# Controller_Board_Interface.net
KiCad netlist of a schematic drawn in Altium Designer
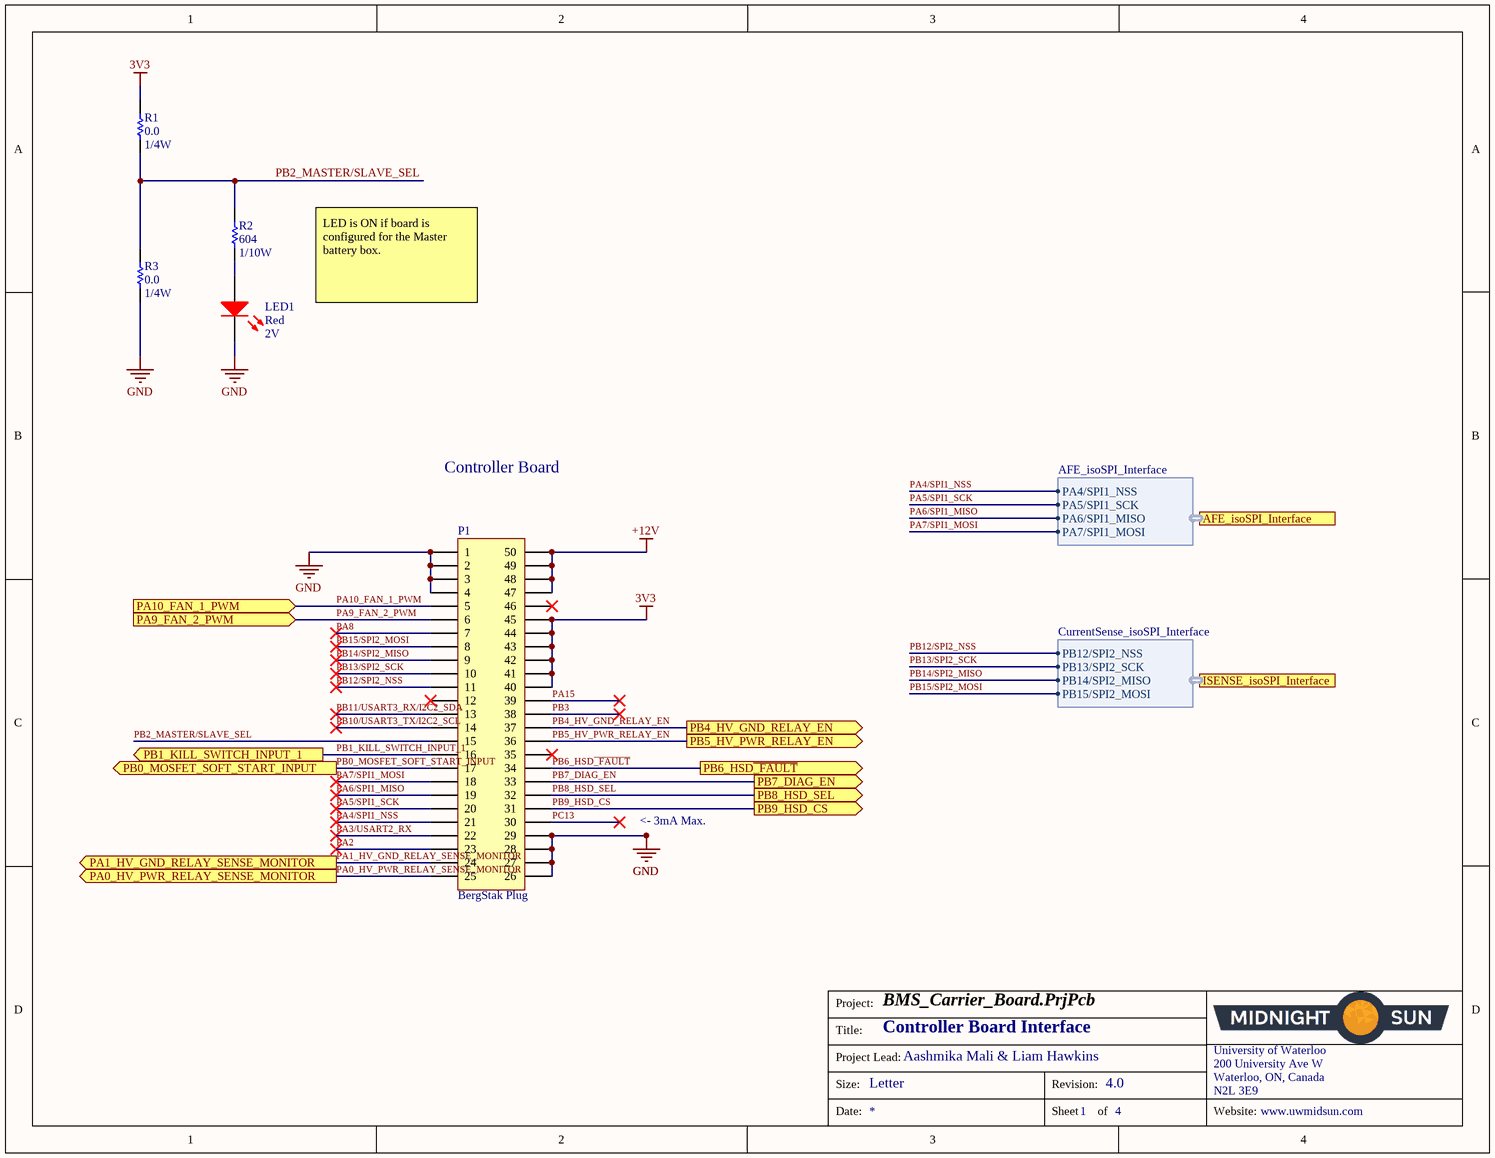
[diagram p0: Controller_Board_Interface.SchDoc]

(export (version "E")
  (design (tool "Eeschema 10.0.6"))
  (components
    (comp (ref "LED1")
      (value "LED RED CLEAR 2V 0603")
      (footprint "LED_0603")
      (description "Red 631nm LED Indication - Discrete 2V 0603 (1608 Metric)")
      (fields
        (field (name "MANUFACTURER") "Wurth Electronics Inc.")
        (field (name "MANUFACTURER PART NUMBER") "150060RS75000")
        (field (name "COLOR") "Red")
        (field (name "VOLTAGE - FORWARD (VF) (TYP)") "2V")
      )
      (libsource (lib "Schematic Diagrams") (part "LED RED CLEAR 2V 0603"))
    )
    (comp (ref "P1")
      (value "CONN 50POS Bergstak Plug 0.02\"")
      (footprint "CONN, Bergstak 50 Pos Plug")
      (description "50 Position Connector Plug, Outer Shroud Contacts Surface Mount Gold")
      (fields (field (name "SERIES") "BergStak Plug"))
      (libsource (lib "Schematic Diagrams") (part "CONN 50POS Bergstak Plug 0.02{dblquote}"))
    )
    (comp (ref "R1")
      (value "RES 0.0 OHM 1/4W 0603")
      (footprint "RES, 0603")
      (description "RES SMD 0.0 OHM JUMPER 1/4W 0603")
      (fields (field (name "RESISTANCE") "0.0") (field (name "POWER (WATTS)") "1/4W"))
      (libsource (lib "Schematic Diagrams") (part "RES 0.0 OHM 1/4W 0603"))
    )
    (comp (ref "R2")
      (value "RES 604 OHM 1% 1/10W 0603")
      (footprint "RES, 0603")
      (description "RES SMD 604 OHM 1% 1/10W 0603")
      (fields
        (field (name "TOLERANCE") "±1%")
        (field (name "RESISTANCE") "604")
        (field (name "POWER") "1/10W")
      )
      (libsource (lib "Schematic Diagrams") (part "RES 604 OHM 1% 1/10W 0603"))
    )
    (comp (ref "R3")
      (value "RES 0.0 OHM 1/4W 0603")
      (footprint "RES, 0603")
      (description "RES SMD 0.0 OHM JUMPER 1/4W 0603")
      (fields (field (name "RESISTANCE") "0.0") (field (name "POWER (WATTS)") "1/4W"))
      (libsource (lib "Schematic Diagrams") (part "RES 0.0 OHM 1/4W 0603"))
    )
  )
  (nets
    (net (code "3") (name "+12V") (class "Default")
      (node (ref "P1") (pin "47") (pinfunction "47_47") (pintype "passive"))
      (node (ref "P1") (pin "48") (pinfunction "48_48") (pintype "passive"))
      (node (ref "P1") (pin "49") (pinfunction "49_49") (pintype "passive"))
      (node (ref "P1") (pin "50") (pinfunction "50_50") (pintype "passive"))
    )
    (net (code "4") (name "/PA0_HV_PWR_RELAY_SENSE_MONITOR") (class "Default")
      (node (ref "P1") (pin "25") (pinfunction "25_25") (pintype "passive"))
    )
    (net (code "5") (name "/PA1_HV_GND_RELAY_SENSE_MONITOR") (class "Default")
      (node (ref "P1") (pin "24") (pinfunction "24_24") (pintype "passive"))
    )
    (net (code "6") (name "/PA2") (class "Default")
      (node (ref "P1") (pin "23") (pinfunction "23_23") (pintype "passive+no_connect"))
    )
    (net (code "7") (name "/PA3{slash}USART2_RX") (class "Default")
      (node (ref "P1") (pin "22") (pinfunction "22_22") (pintype "passive+no_connect"))
    )
    (net (code "8") (name "/PA4{slash}SPI1_NSS") (class "Default")
      (node (ref "P1") (pin "21") (pinfunction "21_21") (pintype "passive"))
    )
    (net (code "9") (name "/PA5{slash}SPI1_SCK") (class "Default")
      (node (ref "P1") (pin "20") (pinfunction "20_20") (pintype "passive"))
    )
    (net (code "10") (name "/PA6{slash}SPI1_MISO") (class "Default")
      (node (ref "P1") (pin "19") (pinfunction "19_19") (pintype "passive"))
    )
    (net (code "11") (name "/PA7{slash}SPI1_MOSI") (class "Default")
      (node (ref "P1") (pin "18") (pinfunction "18_18") (pintype "passive"))
    )
    (net (code "12") (name "/PA8") (class "Default")
      (node (ref "P1") (pin "7") (pinfunction "7_7") (pintype "passive+no_connect"))
    )
    (net (code "13") (name "/PA9_FAN_2_PWM") (class "Default")
      (node (ref "P1") (pin "6") (pinfunction "6_6") (pintype "passive"))
    )
    (net (code "14") (name "/PA10_FAN_1_PWM") (class "Default")
      (node (ref "P1") (pin "5") (pinfunction "5_5") (pintype "passive"))
    )
    (net (code "15") (name "/PA15") (class "Default")
      (node (ref "P1") (pin "39") (pinfunction "39_39") (pintype "passive+no_connect"))
    )
    (net (code "16") (name "/PB0_MOSFET_SOFT_START_INPUT") (class "Default")
      (node (ref "P1") (pin "17") (pinfunction "17_17") (pintype "passive"))
    )
    (net (code "17") (name "/PB1_KILL_SWITCH_INPUT_1") (class "Default")
      (node (ref "P1") (pin "16") (pinfunction "16_16") (pintype "passive"))
    )
    (net (code "18") (name "/PB2_MASTER{slash}SLAVE_SEL") (class "Default")
      (node (ref "P1") (pin "15") (pinfunction "15_15") (pintype "passive"))
      (node (ref "R1") (pin "2") (pinfunction "2_2") (pintype "passive"))
      (node (ref "R2") (pin "1") (pinfunction "1_1") (pintype "passive"))
      (node (ref "R3") (pin "1") (pinfunction "1_1") (pintype "passive"))
    )
    (net (code "19") (name "/PB3") (class "Default")
      (node (ref "P1") (pin "38") (pinfunction "38_38") (pintype "passive+no_connect"))
    )
    (net (code "20") (name "/PB4_HV_GND_RELAY_EN") (class "Default")
      (node (ref "P1") (pin "37") (pinfunction "37_37") (pintype "passive"))
    )
    (net (code "21") (name "/PB5_HV_PWR_RELAY_EN") (class "Default")
      (node (ref "P1") (pin "36") (pinfunction "36_36") (pintype "passive"))
    )
    (net (code "22") (name "/PB6_HSD~{_FAULT}") (class "Default")
      (node (ref "P1") (pin "34") (pinfunction "34_34") (pintype "passive"))
    )
    (net (code "23") (name "/PB7_DIAG_EN") (class "Default")
      (node (ref "P1") (pin "33") (pinfunction "33_33") (pintype "passive"))
    )
    (net (code "24") (name "/PB8_HSD_SEL") (class "Default")
      (node (ref "P1") (pin "32") (pinfunction "32_32") (pintype "passive"))
    )
    (net (code "25") (name "/PB9_HSD_CS") (class "Default")
      (node (ref "P1") (pin "31") (pinfunction "31_31") (pintype "passive"))
    )
    (net (code "26") (name "/PB10{slash}USART3_TX{slash}I2C2_SCL") (class "Default")
      (node (ref "P1") (pin "14") (pinfunction "14_14") (pintype "passive+no_connect"))
    )
    (net (code "27") (name "/PB11{slash}USART3_RX{slash}I2C2_SDA") (class "Default")
      (node (ref "P1") (pin "13") (pinfunction "13_13") (pintype "passive+no_connect"))
    )
    (net (code "28") (name "/PB12{slash}SPI2_NSS") (class "Default")
      (node (ref "P1") (pin "11") (pinfunction "11_11") (pintype "passive"))
    )
    (net (code "29") (name "/PB13{slash}SPI2_SCK") (class "Default")
      (node (ref "P1") (pin "10") (pinfunction "10_10") (pintype "passive"))
    )
    (net (code "30") (name "/PB14{slash}SPI2_MISO") (class "Default")
      (node (ref "P1") (pin "9") (pinfunction "9_9") (pintype "passive"))
    )
    (net (code "31") (name "/PB15{slash}SPI2_MOSI") (class "Default")
      (node (ref "P1") (pin "8") (pinfunction "8_8") (pintype "passive"))
    )
    (net (code "32") (name "/PC13") (class "Default")
      (node (ref "P1") (pin "30") (pinfunction "30_30") (pintype "passive+no_connect"))
    )
    (net (code "35") (name "3V3") (class "Default")
      (node (ref "P1") (pin "40") (pinfunction "40_40") (pintype "passive"))
      (node (ref "P1") (pin "41") (pinfunction "41_41") (pintype "passive"))
      (node (ref "P1") (pin "42") (pinfunction "42_42") (pintype "passive"))
      (node (ref "P1") (pin "43") (pinfunction "43_43") (pintype "passive"))
      (node (ref "P1") (pin "44") (pinfunction "44_44") (pintype "passive"))
      (node (ref "P1") (pin "45") (pinfunction "45_45") (pintype "passive"))
      (node (ref "R1") (pin "1") (pinfunction "1_1") (pintype "passive"))
    )
    (net (code "36") (name "GND") (class "Default")
      (node (ref "LED1") (pin "2") (pinfunction "K_2") (pintype "passive"))
      (node (ref "P1") (pin "1") (pinfunction "1_1") (pintype "passive"))
      (node (ref "P1") (pin "2") (pinfunction "2_2") (pintype "passive"))
      (node (ref "P1") (pin "26") (pinfunction "26_26") (pintype "passive"))
      (node (ref "P1") (pin "27") (pinfunction "27_27") (pintype "passive"))
      (node (ref "P1") (pin "28") (pinfunction "28_28") (pintype "passive"))
      (node (ref "P1") (pin "29") (pinfunction "29_29") (pintype "passive"))
      (node (ref "P1") (pin "3") (pinfunction "3_3") (pintype "passive"))
      (node (ref "P1") (pin "4") (pinfunction "4_4") (pintype "passive"))
      (node (ref "R3") (pin "2") (pinfunction "2_2") (pintype "passive"))
    )
    (net (code "37") (name "Net-(LED1-A)") (class "Default")
      (node (ref "LED1") (pin "1") (pinfunction "A_1") (pintype "passive"))
      (node (ref "R2") (pin "2") (pinfunction "2_2") (pintype "passive"))
    )
    (net (code "38") (name "unconnected-(P1-Pad12)") (class "Default")
      (node (ref "P1") (pin "12") (pinfunction "12_12") (pintype "passive+no_connect"))
    )
    (net (code "39") (name "unconnected-(P1-Pad35)") (class "Default")
      (node (ref "P1") (pin "35") (pinfunction "35_35") (pintype "passive+no_connect"))
    )
    (net (code "40") (name "unconnected-(P1-Pad46)") (class "Default")
      (node (ref "P1") (pin "46") (pinfunction "46_46") (pintype "passive+no_connect"))
    )
  )
)
